# 4_Interface2.net
KiCad netlist of a schematic drawn in Altium Designer
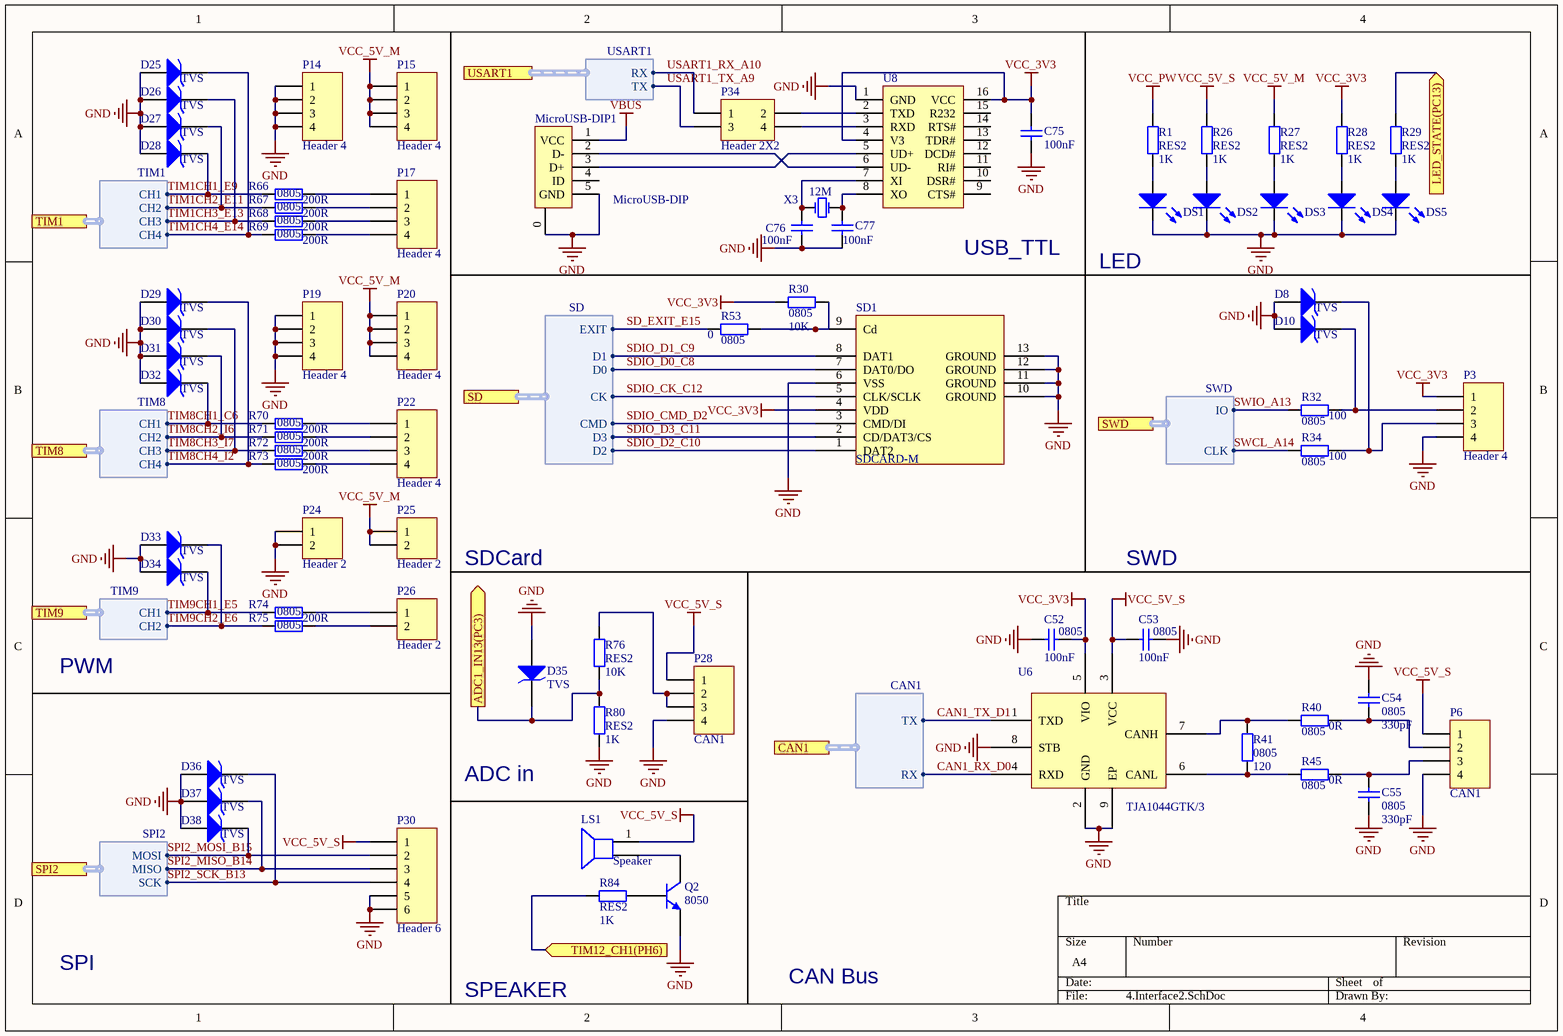
[diagram p0: 4.Interface2.SchDoc]

(export (version "E")
  (design (tool "Eeschema 10.0.6"))
  (components
    (comp (ref "C52")
      (value "0805")
      (footprint "C 0805_M")
      (fields (field (name "ALTIUM_VALUE") "100nF"))
      (libsource (lib "QT") (part "CAP"))
    )
    (comp (ref "C53")
      (value "0805")
      (footprint "C 0805_M")
      (fields (field (name "ALTIUM_VALUE") "100nF"))
      (libsource (lib "QT") (part "CAP"))
    )
    (comp (ref "C54")
      (value "0805")
      (footprint "C 0805_M")
      (fields (field (name "ALTIUM_VALUE") "330pF"))
      (libsource (lib "QT") (part "CAP"))
    )
    (comp (ref "C55")
      (value "0805")
      (footprint "C 0805_M")
      (fields (field (name "ALTIUM_VALUE") "330pF"))
      (libsource (lib "QT") (part "CAP"))
    )
    (comp (ref "C75")
      (value "100nF")
      (footprint "C 0805_L")
      (fields (field (name "Comment") "CAP"))
      (libsource (lib "QT") (part "CAP"))
    )
    (comp (ref "C76")
      (value "100nF")
      (footprint "C 0805_L")
      (fields (field (name "Comment") "CAP"))
      (libsource (lib "QT") (part "CAP"))
    )
    (comp (ref "C77")
      (value "100nF")
      (footprint "C 0805_L")
      (fields (field (name "Comment") "CAP"))
      (libsource (lib "QT") (part "CAP"))
    )
    (comp (ref "D8")
      (value "TVS")
      (footprint "SOD-523")
      (description "High Conductance Fast Diode")
      (fields (field (name "PUBLISHER") "Altium Limited"))
      (libsource (lib "QT") (part "D"))
    )
    (comp (ref "D10")
      (value "TVS")
      (footprint "SOD-523")
      (description "High Conductance Fast Diode")
      (fields (field (name "PUBLISHER") "Altium Limited"))
      (libsource (lib "QT") (part "D"))
    )
    (comp (ref "D25")
      (value "TVS")
      (footprint "SOD-523")
      (description "High Conductance Fast Diode")
      (fields (field (name "PUBLISHER") "Altium Limited"))
      (libsource (lib "QT") (part "D"))
    )
    (comp (ref "D26")
      (value "TVS")
      (footprint "SOD-523")
      (description "High Conductance Fast Diode")
      (fields (field (name "PUBLISHER") "Altium Limited"))
      (libsource (lib "QT") (part "D"))
    )
    (comp (ref "D27")
      (value "TVS")
      (footprint "SOD-523")
      (description "High Conductance Fast Diode")
      (fields (field (name "PUBLISHER") "Altium Limited"))
      (libsource (lib "QT") (part "D"))
    )
    (comp (ref "D28")
      (value "TVS")
      (footprint "SOD-523")
      (description "High Conductance Fast Diode")
      (fields (field (name "PUBLISHER") "Altium Limited"))
      (libsource (lib "QT") (part "D"))
    )
    (comp (ref "D29")
      (value "TVS")
      (footprint "SOD-523")
      (description "High Conductance Fast Diode")
      (fields (field (name "PUBLISHER") "Altium Limited"))
      (libsource (lib "QT") (part "D"))
    )
    (comp (ref "D30")
      (value "TVS")
      (footprint "SOD-523")
      (description "High Conductance Fast Diode")
      (fields (field (name "PUBLISHER") "Altium Limited"))
      (libsource (lib "QT") (part "D"))
    )
    (comp (ref "D31")
      (value "TVS")
      (footprint "SOD-523")
      (description "High Conductance Fast Diode")
      (fields (field (name "PUBLISHER") "Altium Limited"))
      (libsource (lib "QT") (part "D"))
    )
    (comp (ref "D32")
      (value "TVS")
      (footprint "SOD-523")
      (description "High Conductance Fast Diode")
      (fields (field (name "PUBLISHER") "Altium Limited"))
      (libsource (lib "QT") (part "D"))
    )
    (comp (ref "D33")
      (value "TVS")
      (footprint "SOD-523")
      (description "High Conductance Fast Diode")
      (fields (field (name "PUBLISHER") "Altium Limited"))
      (libsource (lib "QT") (part "D"))
    )
    (comp (ref "D34")
      (value "TVS")
      (footprint "SOD-523")
      (description "High Conductance Fast Diode")
      (fields (field (name "PUBLISHER") "Altium Limited"))
      (libsource (lib "QT") (part "D"))
    )
    (comp (ref "D35")
      (value "TVS")
      (footprint "SOD-523")
      (description "High Conductance Fast Diode")
      (fields (field (name "PUBLISHER") "Altium Limited"))
      (libsource (lib "QT") (part "D"))
    )
    (comp (ref "D36")
      (value "TVS")
      (footprint "SOD-523")
      (description "High Conductance Fast Diode")
      (fields (field (name "PUBLISHER") "Altium Limited"))
      (libsource (lib "QT") (part "D"))
    )
    (comp (ref "D37")
      (value "TVS")
      (footprint "SOD-523")
      (description "High Conductance Fast Diode")
      (fields (field (name "PUBLISHER") "Altium Limited"))
      (libsource (lib "QT") (part "D"))
    )
    (comp (ref "D38")
      (value "TVS")
      (footprint "SOD-523")
      (description "High Conductance Fast Diode")
      (fields (field (name "PUBLISHER") "Altium Limited"))
      (libsource (lib "QT") (part "D"))
    )
    (comp (ref "DS1") (value "LED") (footprint "LED 0805B") (libsource (lib "QT") (part "LED")))
    (comp (ref "DS2") (value "LED") (footprint "LED 0805B") (libsource (lib "QT") (part "LED")))
    (comp (ref "DS3") (value "LED") (footprint "LED 0805B") (libsource (lib "QT") (part "LED")))
    (comp (ref "DS4") (value "LED") (footprint "LED 0805B") (libsource (lib "QT") (part "LED")))
    (comp (ref "DS5") (value "LED") (footprint "LED 0805B") (libsource (lib "QT") (part "LED")))
    (comp (ref "LS1")
      (value "Speaker")
      (footprint "BEEP 5x9x5.5")
      (description "Loudspeaker")
      (fields (field (name "PUBLISHER") "Altium Limited"))
      (libsource (lib "QT") (part "Speaker"))
    )
    (comp (ref "MicroUSB-DIP1")
      (value "MicroUSB-DIP")
      (footprint "MICRO_USB_DIP")
      (libsource (lib "PineapplePi-F1") (part "MicroUSB-DIP"))
    )
    (comp (ref "P3")
      (value "Header 4")
      (footprint "KF2EDGK-2.54-WI-4P")
      (description "Header, 4-Pin")
      (fields (field (name "PUBLISHER") "Altium Limited"))
      (libsource (lib "QT") (part "Header 4"))
    )
    (comp (ref "P6")
      (value "CAN1")
      (footprint "KF2EDGK-2.54-WI-4P")
      (description "Header, 4-Pin")
      (fields (field (name "PUBLISHER") "Altium Limited"))
      (libsource (lib "QT") (part "Header 4"))
    )
    (comp (ref "P14")
      (value "Header 4")
      (footprint "HDR2.54-LI-4P")
      (description "Header, 4-Pin")
      (fields (field (name "PUBLISHER") "Altium Limited"))
      (libsource (lib "QT") (part "Header 4"))
    )
    (comp (ref "P15")
      (value "Header 4")
      (footprint "HDR2.54-LI-4P")
      (description "Header, 4-Pin")
      (fields (field (name "PUBLISHER") "Altium Limited"))
      (libsource (lib "QT") (part "Header 4"))
    )
    (comp (ref "P17")
      (value "Header 4")
      (footprint "HDR2.54-LI-4P")
      (description "Header, 4-Pin")
      (fields (field (name "PUBLISHER") "Altium Limited"))
      (libsource (lib "QT") (part "Header 4"))
    )
    (comp (ref "P19")
      (value "Header 4")
      (footprint "HDR2.54-LI-4P")
      (description "Header, 4-Pin")
      (fields (field (name "PUBLISHER") "Altium Limited"))
      (libsource (lib "QT") (part "Header 4"))
    )
    (comp (ref "P20")
      (value "Header 4")
      (footprint "HDR2.54-LI-4P")
      (description "Header, 4-Pin")
      (fields (field (name "PUBLISHER") "Altium Limited"))
      (libsource (lib "QT") (part "Header 4"))
    )
    (comp (ref "P22")
      (value "Header 4")
      (footprint "HDR2.54-LI-4P")
      (description "Header, 4-Pin")
      (fields (field (name "PUBLISHER") "Altium Limited"))
      (libsource (lib "QT") (part "Header 4"))
    )
    (comp (ref "P24")
      (value "Header 2")
      (footprint "HDR2.54-LI-2P")
      (description "Header, 2-Pin")
      (fields (field (name "PUBLISHER") "Altium Limited"))
      (libsource (lib "QT") (part "Header 2"))
    )
    (comp (ref "P25")
      (value "Header 2")
      (footprint "HDR2.54-LI-2P")
      (description "Header, 2-Pin")
      (fields (field (name "PUBLISHER") "Altium Limited"))
      (libsource (lib "QT") (part "Header 2"))
    )
    (comp (ref "P26")
      (value "Header 2")
      (footprint "HDR2.54-LI-2P")
      (description "Header, 2-Pin")
      (fields (field (name "PUBLISHER") "Altium Limited"))
      (libsource (lib "QT") (part "Header 2"))
    )
    (comp (ref "P28")
      (value "CAN1")
      (footprint "KF2EDGK-2.54-WI-4P")
      (description "Header, 4-Pin")
      (fields (field (name "PUBLISHER") "Altium Limited"))
      (libsource (lib "QT") (part "Header 4"))
    )
    (comp (ref "P30")
      (value "Header 6")
      (footprint "KF2EDGK-2.54-WI-6P")
      (description "Header, 6-Pin")
      (fields (field (name "PUBLISHER") "Altium Limited"))
      (libsource (lib "Miscellaneous Connectors") (part "Header 6"))
    )
    (comp (ref "P34")
      (value "Header 2X2")
      (footprint "HDR2.54-LI-2x2P")
      (description "Header, 2-Pin, Dual row")
      (fields (field (name "PUBLISHER") "Altium Limited"))
      (libsource (lib "QT") (part "Header 2X2"))
    )
    (comp (ref "Q2")
      (value "8050")
      (footprint "SOT23-3L")
      (description "NPN Bipolar Transistor")
      (fields (field (name "PUBLISHER") "Altium Limited"))
      (libsource (lib "QT") (part "NPN  SOT"))
    )
    (comp (ref "R1")
      (value "RES2")
      (footprint "R 0805_L")
      (description "Resistor")
      (fields (field (name "ALTIUM_VALUE") "1K") (field (name "PUBLISHER") "Altium Limited"))
      (libsource (lib "") (part "RES2_1"))
    )
    (comp (ref "R26")
      (value "RES2")
      (footprint "R 0805_L")
      (description "Resistor")
      (fields (field (name "ALTIUM_VALUE") "1K") (field (name "PUBLISHER") "Altium Limited"))
      (libsource (lib "") (part "RES2_1"))
    )
    (comp (ref "R27")
      (value "RES2")
      (footprint "R 0805_L")
      (description "Resistor")
      (fields (field (name "ALTIUM_VALUE") "1K") (field (name "PUBLISHER") "Altium Limited"))
      (libsource (lib "") (part "RES2_1"))
    )
    (comp (ref "R28")
      (value "RES2")
      (footprint "R 0805_L")
      (description "Resistor")
      (fields (field (name "ALTIUM_VALUE") "1K") (field (name "PUBLISHER") "Altium Limited"))
      (libsource (lib "") (part "RES2_1"))
    )
    (comp (ref "R29")
      (value "RES2")
      (footprint "R 0805_L")
      (description "Resistor")
      (fields (field (name "ALTIUM_VALUE") "1K") (field (name "PUBLISHER") "Altium Limited"))
      (libsource (lib "") (part "RES2_1"))
    )
    (comp (ref "R30")
      (value "0805")
      (footprint "R 0805_L")
      (description "Resistor")
      (fields (field (name "ALTIUM_VALUE") "10K") (field (name "PUBLISHER") "Altium Limited"))
      (libsource (lib "QT") (part "RES2"))
    )
    (comp (ref "R32")
      (value "0805")
      (footprint "R 0805_L")
      (description "Resistor")
      (fields (field (name "ALTIUM_VALUE") "100") (field (name "PUBLISHER") "Altium Limited"))
      (libsource (lib "") (part "RES2_2"))
    )
    (comp (ref "R34")
      (value "0805")
      (footprint "R 0805_L")
      (description "Resistor")
      (fields (field (name "ALTIUM_VALUE") "100") (field (name "PUBLISHER") "Altium Limited"))
      (libsource (lib "") (part "RES2_2"))
    )
    (comp (ref "R40")
      (value "0805")
      (footprint "R 0805_L")
      (description "Resistor")
      (fields (field (name "ALTIUM_VALUE") "0R") (field (name "PUBLISHER") "Altium Limited"))
      (libsource (lib "QT") (part "RES2"))
    )
    (comp (ref "R41")
      (value "0805")
      (footprint "R 0805_L")
      (description "Resistor")
      (fields (field (name "ALTIUM_VALUE") "120") (field (name "PUBLISHER") "Altium Limited"))
      (libsource (lib "") (part "RES2_1"))
    )
    (comp (ref "R45")
      (value "0805")
      (footprint "R 0805_L")
      (description "Resistor")
      (fields (field (name "ALTIUM_VALUE") "0R") (field (name "PUBLISHER") "Altium Limited"))
      (libsource (lib "QT") (part "RES2"))
    )
    (comp (ref "R53")
      (value "0805")
      (footprint "R 0805_L")
      (description "Resistor")
      (fields (field (name "ALTIUM_VALUE") "0") (field (name "PUBLISHER") "Altium Limited"))
      (libsource (lib "") (part "RES2_2"))
    )
    (comp (ref "R66")
      (value "0805")
      (footprint "R 0805_L")
      (description "Resistor")
      (fields (field (name "ALTIUM_VALUE") "200R") (field (name "PUBLISHER") "Altium Limited"))
      (libsource (lib "") (part "RES2_2"))
    )
    (comp (ref "R67")
      (value "0805")
      (footprint "R 0805_L")
      (description "Resistor")
      (fields (field (name "ALTIUM_VALUE") "200R") (field (name "PUBLISHER") "Altium Limited"))
      (libsource (lib "") (part "RES2_2"))
    )
    (comp (ref "R68")
      (value "0805")
      (footprint "R 0805_L")
      (description "Resistor")
      (fields (field (name "ALTIUM_VALUE") "200R") (field (name "PUBLISHER") "Altium Limited"))
      (libsource (lib "") (part "RES2_2"))
    )
    (comp (ref "R69")
      (value "0805")
      (footprint "R 0805_L")
      (description "Resistor")
      (fields (field (name "ALTIUM_VALUE") "200R") (field (name "PUBLISHER") "Altium Limited"))
      (libsource (lib "") (part "RES2_2"))
    )
    (comp (ref "R70")
      (value "0805")
      (footprint "R 0805_L")
      (description "Resistor")
      (fields (field (name "ALTIUM_VALUE") "200R") (field (name "PUBLISHER") "Altium Limited"))
      (libsource (lib "") (part "RES2_2"))
    )
    (comp (ref "R71")
      (value "0805")
      (footprint "R 0805_L")
      (description "Resistor")
      (fields (field (name "ALTIUM_VALUE") "200R") (field (name "PUBLISHER") "Altium Limited"))
      (libsource (lib "") (part "RES2_2"))
    )
    (comp (ref "R72")
      (value "0805")
      (footprint "R 0805_L")
      (description "Resistor")
      (fields (field (name "ALTIUM_VALUE") "200R") (field (name "PUBLISHER") "Altium Limited"))
      (libsource (lib "") (part "RES2_2"))
    )
    (comp (ref "R73")
      (value "0805")
      (footprint "R 0805_L")
      (description "Resistor")
      (fields (field (name "ALTIUM_VALUE") "200R") (field (name "PUBLISHER") "Altium Limited"))
      (libsource (lib "") (part "RES2_2"))
    )
    (comp (ref "R74")
      (value "0805")
      (footprint "R 0805_L")
      (description "Resistor")
      (fields (field (name "ALTIUM_VALUE") "200R") (field (name "PUBLISHER") "Altium Limited"))
      (libsource (lib "") (part "RES2_2"))
    )
    (comp (ref "R75")
      (value "0805")
      (footprint "R 0805_L")
      (description "Resistor")
      (fields (field (name "PUBLISHER") "Altium Limited"))
      (libsource (lib "") (part "RES2_2"))
    )
    (comp (ref "R76")
      (value "RES2")
      (footprint "R 0805_L")
      (description "Resistor")
      (fields (field (name "ALTIUM_VALUE") "10K") (field (name "PUBLISHER") "Altium Limited"))
      (libsource (lib "") (part "RES2_1"))
    )
    (comp (ref "R80")
      (value "RES2")
      (footprint "R 0805_L")
      (description "Resistor")
      (fields (field (name "ALTIUM_VALUE") "1K") (field (name "PUBLISHER") "Altium Limited"))
      (libsource (lib "") (part "RES2_1"))
    )
    (comp (ref "R84")
      (value "RES2")
      (footprint "R 0805_L")
      (description "Resistor")
      (fields (field (name "ALTIUM_VALUE") "1K") (field (name "PUBLISHER") "Altium Limited"))
      (libsource (lib "QT") (part "RES2"))
    )
    (comp (ref "SD1")
      (value "SDCARD-M")
      (footprint "SDCARD-M")
      (description "TF卡槽")
      (libsource (lib "Fszhang") (part "SDCARD-M"))
    )
    (comp (ref "U6")
      (value "TJA1044GTK/3")
      (footprint "HVSON8")
      (libsource (lib "常用元件库") (part "TJA1044GTK/3"))
    )
    (comp (ref "U8") (value "CH340G") (footprint "SOP16_M") (libsource (lib "史福祥库") (part "CH340G")))
    (comp (ref "X3") (value "12M") (footprint "OSC HC-49S") (libsource (lib "QT") (part "YX")))
  )
  (nets
    (net (code "9") (name "/ADC1_IN13(PC3)") (class "Default")
      (node (ref "D35") (pin "2") (pinfunction "K_2") (pintype "passive"))
      (node (ref "R76") (pin "1") (pinfunction "1_1") (pintype "passive"))
      (node (ref "R80") (pin "2") (pinfunction "2_2") (pintype "passive"))
    )
    (net (code "10") (name "/CAN1_RX_D0") (class "Default")
      (node (ref "U6") (pin "4") (pinfunction "RXD_4") (pintype "passive"))
    )
    (net (code "11") (name "/CAN1_TX_D1") (class "Default")
      (node (ref "U6") (pin "1") (pinfunction "TXD_1") (pintype "passive"))
    )
    (net (code "12") (name "/LED_STATE(PC13)") (class "Default")
      (node (ref "R29") (pin "2") (pinfunction "2_2") (pintype "passive"))
    )
    (net (code "13") (name "/SDIO_CK_C12") (class "Default")
      (node (ref "SD1") (pin "5") (pinfunction "CLK/SCLK_5") (pintype "passive"))
    )
    (net (code "14") (name "/SDIO_CMD_D2") (class "Default")
      (node (ref "SD1") (pin "3") (pinfunction "CMD/DI_3") (pintype "passive"))
    )
    (net (code "15") (name "/SDIO_D0_C8") (class "Default")
      (node (ref "SD1") (pin "7") (pinfunction "DAT0/DO_7") (pintype "passive"))
    )
    (net (code "16") (name "/SDIO_D1_C9") (class "Default")
      (node (ref "SD1") (pin "8") (pinfunction "DAT1_8") (pintype "passive"))
    )
    (net (code "17") (name "/SDIO_D2_C10") (class "Default")
      (node (ref "SD1") (pin "1") (pinfunction "DAT2_1") (pintype "passive"))
    )
    (net (code "18") (name "/SDIO_D3_C11") (class "Default")
      (node (ref "SD1") (pin "2") (pinfunction "CD/DAT3/CS_2") (pintype "passive"))
    )
    (net (code "19") (name "/SD_EXIT_E15") (class "Default")
      (node (ref "R53") (pin "1") (pinfunction "1_1") (pintype "passive"))
    )
    (net (code "20") (name "/SPI2_MISO_B14") (class "Default")
      (node (ref "D37") (pin "2") (pinfunction "K_2") (pintype "passive"))
      (node (ref "P30") (pin "3") (pinfunction "3_3") (pintype "passive"))
    )
    (net (code "21") (name "/SPI2_MOSI_B15") (class "Default")
      (node (ref "D38") (pin "2") (pinfunction "K_2") (pintype "passive"))
      (node (ref "P30") (pin "2") (pinfunction "2_2") (pintype "passive"))
    )
    (net (code "22") (name "/SPI2_SCK_B13") (class "Default")
      (node (ref "D36") (pin "2") (pinfunction "K_2") (pintype "passive"))
      (node (ref "P30") (pin "4") (pinfunction "4_4") (pintype "passive"))
    )
    (net (code "23") (name "/SWCL_A14") (class "Default")
      (node (ref "R34") (pin "1") (pinfunction "1_1") (pintype "passive"))
    )
    (net (code "24") (name "/SWIO_A13") (class "Default")
      (node (ref "R32") (pin "1") (pinfunction "1_1") (pintype "passive"))
    )
    (net (code "25") (name "/TIM1CH1_E9") (class "Default")
      (node (ref "D28") (pin "2") (pinfunction "K_2") (pintype "passive"))
      (node (ref "R66") (pin "1") (pinfunction "1_1") (pintype "passive"))
    )
    (net (code "26") (name "/TIM1CH2_E11") (class "Default")
      (node (ref "D27") (pin "2") (pinfunction "K_2") (pintype "passive"))
      (node (ref "R67") (pin "1") (pinfunction "1_1") (pintype "passive"))
    )
    (net (code "27") (name "/TIM1CH3_E13") (class "Default")
      (node (ref "D26") (pin "2") (pinfunction "K_2") (pintype "passive"))
      (node (ref "R68") (pin "1") (pinfunction "1_1") (pintype "passive"))
    )
    (net (code "28") (name "/TIM1CH4_E14") (class "Default")
      (node (ref "D25") (pin "2") (pinfunction "K_2") (pintype "passive"))
      (node (ref "R69") (pin "1") (pinfunction "1_1") (pintype "passive"))
    )
    (net (code "29") (name "/TIM8CH1_C6") (class "Default")
      (node (ref "D32") (pin "2") (pinfunction "K_2") (pintype "passive"))
      (node (ref "R70") (pin "1") (pinfunction "1_1") (pintype "passive"))
    )
    (net (code "30") (name "/TIM8CH2_I6") (class "Default")
      (node (ref "D31") (pin "2") (pinfunction "K_2") (pintype "passive"))
      (node (ref "R71") (pin "1") (pinfunction "1_1") (pintype "passive"))
    )
    (net (code "31") (name "/TIM8CH3_I7") (class "Default")
      (node (ref "D30") (pin "2") (pinfunction "K_2") (pintype "passive"))
      (node (ref "R72") (pin "1") (pinfunction "1_1") (pintype "passive"))
    )
    (net (code "32") (name "/TIM8CH4_I2") (class "Default")
      (node (ref "D29") (pin "2") (pinfunction "K_2") (pintype "passive"))
      (node (ref "R73") (pin "1") (pinfunction "1_1") (pintype "passive"))
    )
    (net (code "33") (name "/TIM9CH1_E5") (class "Default")
      (node (ref "D34") (pin "2") (pinfunction "K_2") (pintype "passive"))
      (node (ref "R74") (pin "1") (pinfunction "1_1") (pintype "passive"))
    )
    (net (code "34") (name "/TIM9CH2_E6") (class "Default")
      (node (ref "D33") (pin "2") (pinfunction "K_2") (pintype "passive"))
      (node (ref "R75") (pin "1") (pinfunction "1_1") (pintype "passive"))
    )
    (net (code "35") (name "/TIM12_CH1(PH6)") (class "Default")
      (node (ref "R84") (pin "2") (pinfunction "2_2") (pintype "passive"))
    )
    (net (code "36") (name "/USART1_RX_A10") (class "Default")
      (node (ref "P34") (pin "1") (pinfunction "1_1") (pintype "passive"))
    )
    (net (code "37") (name "/USART1_TX_A9") (class "Default")
      (node (ref "P34") (pin "3") (pinfunction "3_3") (pintype "passive"))
    )
    (net (code "46") (name "GND") (class "Default")
      (node (ref "C52") (pin "1") (pinfunction "1_1") (pintype "passive"))
      (node (ref "C53") (pin "2") (pinfunction "2_2") (pintype "passive"))
      (node (ref "C54") (pin "2") (pinfunction "2_2") (pintype "passive"))
      (node (ref "C55") (pin "1") (pinfunction "1_1") (pintype "passive"))
      (node (ref "C75") (pin "1") (pinfunction "1_1") (pintype "passive"))
      (node (ref "C76") (pin "1") (pinfunction "1_1") (pintype "passive"))
      (node (ref "C77") (pin "1") (pinfunction "1_1") (pintype "passive"))
      (node (ref "D10") (pin "1") (pinfunction "A_1") (pintype "passive"))
      (node (ref "D25") (pin "1") (pinfunction "A_1") (pintype "passive"))
      (node (ref "D26") (pin "1") (pinfunction "A_1") (pintype "passive"))
      (node (ref "D27") (pin "1") (pinfunction "A_1") (pintype "passive"))
      (node (ref "D28") (pin "1") (pinfunction "A_1") (pintype "passive"))
      (node (ref "D29") (pin "1") (pinfunction "A_1") (pintype "passive"))
      (node (ref "D30") (pin "1") (pinfunction "A_1") (pintype "passive"))
      (node (ref "D31") (pin "1") (pinfunction "A_1") (pintype "passive"))
      (node (ref "D32") (pin "1") (pinfunction "A_1") (pintype "passive"))
      (node (ref "D33") (pin "1") (pinfunction "A_1") (pintype "passive"))
      (node (ref "D34") (pin "1") (pinfunction "A_1") (pintype "passive"))
      (node (ref "D35") (pin "1") (pinfunction "A_1") (pintype "passive"))
      (node (ref "D36") (pin "1") (pinfunction "A_1") (pintype "passive"))
      (node (ref "D37") (pin "1") (pinfunction "A_1") (pintype "passive"))
      (node (ref "D38") (pin "1") (pinfunction "A_1") (pintype "passive"))
      (node (ref "D8") (pin "1") (pinfunction "A_1") (pintype "passive"))
      (node (ref "DS1") (pin "2") (pinfunction "K_2") (pintype "passive"))
      (node (ref "DS2") (pin "2") (pinfunction "K_2") (pintype "passive"))
      (node (ref "DS3") (pin "2") (pinfunction "K_2") (pintype "passive"))
      (node (ref "DS4") (pin "2") (pinfunction "K_2") (pintype "passive"))
      (node (ref "DS5") (pin "2") (pinfunction "K_2") (pintype "passive"))
      (node (ref "MicroUSB-DIP1") (pin "0") (pintype "passive"))
      (node (ref "MicroUSB-DIP1") (pin "5") (pinfunction "GND_5") (pintype "power_in"))
      (node (ref "P14") (pin "1") (pinfunction "1_1") (pintype "passive"))
      (node (ref "P14") (pin "2") (pinfunction "2_2") (pintype "passive"))
      (node (ref "P14") (pin "3") (pinfunction "3_3") (pintype "passive"))
      (node (ref "P14") (pin "4") (pinfunction "4_4") (pintype "passive"))
      (node (ref "P19") (pin "1") (pinfunction "1_1") (pintype "passive"))
      (node (ref "P19") (pin "2") (pinfunction "2_2") (pintype "passive"))
      (node (ref "P19") (pin "3") (pinfunction "3_3") (pintype "passive"))
      (node (ref "P19") (pin "4") (pinfunction "4_4") (pintype "passive"))
      (node (ref "P24") (pin "1") (pinfunction "1_1") (pintype "passive"))
      (node (ref "P24") (pin "2") (pinfunction "2_2") (pintype "passive"))
      (node (ref "P28") (pin "4") (pinfunction "4_4") (pintype "passive"))
      (node (ref "P3") (pin "4") (pinfunction "4_4") (pintype "passive"))
      (node (ref "P30") (pin "5") (pinfunction "5_5") (pintype "passive"))
      (node (ref "P30") (pin "6") (pinfunction "6_6") (pintype "passive"))
      (node (ref "P6") (pin "4") (pinfunction "4_4") (pintype "passive"))
      (node (ref "Q2") (pin "2") (pinfunction "E_2") (pintype "passive"))
      (node (ref "R80") (pin "1") (pinfunction "1_1") (pintype "passive"))
      (node (ref "SD1") (pin "10") (pinfunction "GROUND_10") (pintype "passive"))
      (node (ref "SD1") (pin "11") (pinfunction "GROUND_11") (pintype "passive"))
      (node (ref "SD1") (pin "12") (pinfunction "GROUND_12") (pintype "passive"))
      (node (ref "SD1") (pin "13") (pinfunction "GROUND_13") (pintype "passive"))
      (node (ref "SD1") (pin "6") (pinfunction "VSS_6") (pintype "passive"))
      (node (ref "U6") (pin "2") (pinfunction "GND_2") (pintype "passive"))
      (node (ref "U6") (pin "8") (pinfunction "STB_8") (pintype "passive"))
      (node (ref "U6") (pin "9") (pinfunction "EP_9") (pintype "passive"))
      (node (ref "U8") (pin "1") (pinfunction "GND_1") (pintype "passive"))
    )
    (net (code "47") (name "Net-(C54-Pad1)") (class "Default")
      (node (ref "C54") (pin "1") (pinfunction "1_1") (pintype "passive"))
      (node (ref "P6") (pin "2") (pinfunction "2_2") (pintype "passive"))
      (node (ref "R40") (pin "1") (pinfunction "1_1") (pintype "passive"))
    )
    (net (code "48") (name "Net-(C55-Pad2)") (class "Default")
      (node (ref "C55") (pin "2") (pinfunction "2_2") (pintype "passive"))
      (node (ref "P6") (pin "3") (pinfunction "3_3") (pintype "passive"))
      (node (ref "R45") (pin "1") (pinfunction "1_1") (pintype "passive"))
    )
    (net (code "49") (name "Net-(D8-K)") (class "Default")
      (node (ref "D8") (pin "2") (pinfunction "K_2") (pintype "passive"))
      (node (ref "P3") (pin "3") (pinfunction "3_3") (pintype "passive"))
      (node (ref "R34") (pin "2") (pinfunction "2_2") (pintype "passive"))
    )
    (net (code "50") (name "Net-(D10-K)") (class "Default")
      (node (ref "D10") (pin "2") (pinfunction "K_2") (pintype "passive"))
      (node (ref "P3") (pin "2") (pinfunction "2_2") (pintype "passive"))
      (node (ref "R32") (pin "2") (pinfunction "2_2") (pintype "passive"))
    )
    (net (code "51") (name "Net-(DS1-A)") (class "Default")
      (node (ref "DS1") (pin "1") (pinfunction "A_1") (pintype "passive"))
      (node (ref "R1") (pin "1") (pinfunction "1_1") (pintype "passive"))
    )
    (net (code "52") (name "Net-(DS2-A)") (class "Default")
      (node (ref "DS2") (pin "1") (pinfunction "A_1") (pintype "passive"))
      (node (ref "R26") (pin "1") (pinfunction "1_1") (pintype "passive"))
    )
    (net (code "53") (name "Net-(DS3-A)") (class "Default")
      (node (ref "DS3") (pin "1") (pinfunction "A_1") (pintype "passive"))
      (node (ref "R27") (pin "1") (pinfunction "1_1") (pintype "passive"))
    )
    (net (code "54") (name "Net-(DS4-A)") (class "Default")
      (node (ref "DS4") (pin "1") (pinfunction "A_1") (pintype "passive"))
      (node (ref "R28") (pin "1") (pinfunction "1_1") (pintype "passive"))
    )
    (net (code "55") (name "Net-(DS5-A)") (class "Default")
      (node (ref "DS5") (pin "1") (pinfunction "A_1") (pintype "passive"))
      (node (ref "R29") (pin "1") (pinfunction "1_1") (pintype "passive"))
    )
    (net (code "56") (name "Net-(MicroUSB-DIP1-D+)") (class "Default")
      (node (ref "MicroUSB-DIP1") (pin "3") (pinfunction "D+_3") (pintype "power_in"))
      (node (ref "U8") (pin "5") (pinfunction "UD+_5") (pintype "passive"))
    )
    (net (code "57") (name "Net-(MicroUSB-DIP1-D-)") (class "Default")
      (node (ref "MicroUSB-DIP1") (pin "2") (pinfunction "D-_2") (pintype "power_in"))
      (node (ref "U8") (pin "6") (pinfunction "UD-_6") (pintype "passive"))
    )
    (net (code "58") (name "Net-(P17-Pad1)") (class "Default")
      (node (ref "P17") (pin "1") (pinfunction "1_1") (pintype "passive"))
      (node (ref "R66") (pin "2") (pinfunction "2_2") (pintype "passive"))
    )
    (net (code "59") (name "Net-(P17-Pad2)") (class "Default")
      (node (ref "P17") (pin "2") (pinfunction "2_2") (pintype "passive"))
      (node (ref "R67") (pin "2") (pinfunction "2_2") (pintype "passive"))
    )
    (net (code "60") (name "Net-(P17-Pad3)") (class "Default")
      (node (ref "P17") (pin "3") (pinfunction "3_3") (pintype "passive"))
      (node (ref "R68") (pin "2") (pinfunction "2_2") (pintype "passive"))
    )
    (net (code "61") (name "Net-(P17-Pad4)") (class "Default")
      (node (ref "P17") (pin "4") (pinfunction "4_4") (pintype "passive"))
      (node (ref "R69") (pin "2") (pinfunction "2_2") (pintype "passive"))
    )
    (net (code "62") (name "Net-(P22-Pad1)") (class "Default")
      (node (ref "P22") (pin "1") (pinfunction "1_1") (pintype "passive"))
      (node (ref "R70") (pin "2") (pinfunction "2_2") (pintype "passive"))
    )
    (net (code "63") (name "Net-(P22-Pad2)") (class "Default")
      (node (ref "P22") (pin "2") (pinfunction "2_2") (pintype "passive"))
      (node (ref "R71") (pin "2") (pinfunction "2_2") (pintype "passive"))
    )
    (net (code "64") (name "Net-(P22-Pad3)") (class "Default")
      (node (ref "P22") (pin "3") (pinfunction "3_3") (pintype "passive"))
      (node (ref "R72") (pin "2") (pinfunction "2_2") (pintype "passive"))
    )
    (net (code "65") (name "Net-(P22-Pad4)") (class "Default")
      (node (ref "P22") (pin "4") (pinfunction "4_4") (pintype "passive"))
      (node (ref "R73") (pin "2") (pinfunction "2_2") (pintype "passive"))
    )
    (net (code "66") (name "Net-(P26-Pad1)") (class "Default")
      (node (ref "P26") (pin "1") (pinfunction "1_1") (pintype "passive"))
      (node (ref "R74") (pin "2") (pinfunction "2_2") (pintype "passive"))
    )
    (net (code "67") (name "Net-(P26-Pad2)") (class "Default")
      (node (ref "P26") (pin "2") (pinfunction "2_2") (pintype "passive"))
      (node (ref "R75") (pin "2") (pinfunction "2_2") (pintype "passive"))
    )
    (net (code "68") (name "Net-(P28-Pad2)") (class "Default")
      (node (ref "P28") (pin "2") (pinfunction "2_2") (pintype "passive"))
      (node (ref "P28") (pin "3") (pinfunction "3_3") (pintype "passive"))
      (node (ref "R76") (pin "2") (pinfunction "2_2") (pintype "passive"))
    )
    (net (code "69") (name "Net-(Q2-B)") (class "Default")
      (node (ref "Q2") (pin "1") (pinfunction "B_1") (pintype "passive"))
      (node (ref "R84") (pin "1") (pinfunction "1_1") (pintype "passive"))
    )
    (net (code "70") (name "Net-(Q2-C)") (class "Default")
      (node (ref "LS1") (pin "2") (pinfunction "2_2") (pintype "passive"))
      (node (ref "Q2") (pin "3") (pinfunction "C_3") (pintype "passive"))
    )
    (net (code "71") (name "Net-(SD1-Cd)") (class "Default")
      (node (ref "R30") (pin "1") (pinfunction "1_1") (pintype "passive"))
      (node (ref "R53") (pin "2") (pinfunction "2_2") (pintype "passive"))
      (node (ref "SD1") (pin "9") (pinfunction "Cd_9") (pintype "passive"))
    )
    (net (code "72") (name "Net-(U6-CANH)") (class "Default")
      (node (ref "R40") (pin "2") (pinfunction "2_2") (pintype "passive"))
      (node (ref "R41") (pin "2") (pinfunction "2_2") (pintype "passive"))
      (node (ref "U6") (pin "7") (pinfunction "CANH_7") (pintype "passive"))
    )
    (net (code "73") (name "Net-(U6-CANL)") (class "Default")
      (node (ref "R41") (pin "1") (pinfunction "1_1") (pintype "passive"))
      (node (ref "R45") (pin "2") (pinfunction "2_2") (pintype "passive"))
      (node (ref "U6") (pin "6") (pinfunction "CANL_6") (pintype "passive"))
    )
    (net (code "74") (name "Net-(U8-RXD)") (class "Default")
      (node (ref "P34") (pin "4") (pinfunction "4_4") (pintype "passive"))
      (node (ref "U8") (pin "3") (pinfunction "RXD_3") (pintype "passive"))
    )
    (net (code "75") (name "Net-(U8-TXD)") (class "Default")
      (node (ref "P34") (pin "2") (pinfunction "2_2") (pintype "passive"))
      (node (ref "U8") (pin "2") (pinfunction "TXD_2") (pintype "passive"))
    )
    (net (code "76") (name "Net-(U8-XI)") (class "Default")
      (node (ref "C76") (pin "2") (pinfunction "2_2") (pintype "passive"))
      (node (ref "U8") (pin "7") (pinfunction "XI_7") (pintype "passive"))
      (node (ref "X3") (pin "1") (pinfunction "OSC1_1") (pintype "passive"))
    )
    (net (code "77") (name "Net-(U8-XO)") (class "Default")
      (node (ref "C77") (pin "2") (pinfunction "2_2") (pintype "passive"))
      (node (ref "U8") (pin "8") (pinfunction "XO_8") (pintype "passive"))
      (node (ref "X3") (pin "2") (pinfunction "OSC2_2") (pintype "passive"))
    )
    (net (code "78") (name "VBUS") (class "Default")
      (node (ref "MicroUSB-DIP1") (pin "1") (pinfunction "VCC_1") (pintype "power_in"))
    )
    (net (code "79") (name "VCC_3V3") (class "Default")
      (node (ref "C52") (pin "2") (pinfunction "2_2") (pintype "passive"))
      (node (ref "C75") (pin "2") (pinfunction "2_2") (pintype "passive"))
      (node (ref "P3") (pin "1") (pinfunction "1_1") (pintype "passive"))
      (node (ref "R28") (pin "2") (pinfunction "2_2") (pintype "passive"))
      (node (ref "R30") (pin "2") (pinfunction "2_2") (pintype "passive"))
      (node (ref "SD1") (pin "4") (pinfunction "VDD_4") (pintype "passive"))
      (node (ref "U6") (pin "5") (pinfunction "VIO_5") (pintype "passive"))
      (node (ref "U8") (pin "16") (pinfunction "VCC_16") (pintype "passive"))
      (node (ref "U8") (pin "4") (pinfunction "V3_4") (pintype "passive"))
    )
    (net (code "80") (name "VCC_5V_M") (class "Default")
      (node (ref "P15") (pin "1") (pinfunction "1_1") (pintype "passive"))
      (node (ref "P15") (pin "2") (pinfunction "2_2") (pintype "passive"))
      (node (ref "P15") (pin "3") (pinfunction "3_3") (pintype "passive"))
      (node (ref "P15") (pin "4") (pinfunction "4_4") (pintype "passive"))
      (node (ref "P20") (pin "1") (pinfunction "1_1") (pintype "passive"))
      (node (ref "P20") (pin "2") (pinfunction "2_2") (pintype "passive"))
      (node (ref "P20") (pin "3") (pinfunction "3_3") (pintype "passive"))
      (node (ref "P20") (pin "4") (pinfunction "4_4") (pintype "passive"))
      (node (ref "P25") (pin "1") (pinfunction "1_1") (pintype "passive"))
      (node (ref "P25") (pin "2") (pinfunction "2_2") (pintype "passive"))
      (node (ref "R27") (pin "2") (pinfunction "2_2") (pintype "passive"))
    )
    (net (code "81") (name "VCC_5V_S") (class "Default")
      (node (ref "C53") (pin "1") (pinfunction "1_1") (pintype "passive"))
      (node (ref "LS1") (pin "1") (pinfunction "1_1") (pintype "passive"))
      (node (ref "P28") (pin "1") (pinfunction "1_1") (pintype "passive"))
      (node (ref "P30") (pin "1") (pinfunction "1_1") (pintype "passive"))
      (node (ref "P6") (pin "1") (pinfunction "1_1") (pintype "passive"))
      (node (ref "R26") (pin "2") (pinfunction "2_2") (pintype "passive"))
      (node (ref "U6") (pin "3") (pinfunction "VCC_3") (pintype "passive"))
    )
    (net (code "82") (name "VCC_PW") (class "Default")
      (node (ref "R1") (pin "2") (pinfunction "2_2") (pintype "passive"))
    )
    (net (code "83") (name "unconnected-(MicroUSB-DIP1-ID-Pad4)") (class "Default")
      (node (ref "MicroUSB-DIP1") (pin "4") (pinfunction "ID_4") (pintype "passive"))
    )
    (net (code "84") (name "unconnected-(U8-CTS#-Pad9)") (class "Default")
      (node (ref "U8") (pin "9") (pinfunction "CTS#_9") (pintype "passive"))
    )
    (net (code "85") (name "unconnected-(U8-DCD#-Pad12)") (class "Default")
      (node (ref "U8") (pin "12") (pinfunction "DCD#_12") (pintype "passive"))
    )
    (net (code "86") (name "unconnected-(U8-DSR#-Pad10)") (class "Default")
      (node (ref "U8") (pin "10") (pinfunction "DSR#_10") (pintype "passive"))
    )
    (net (code "87") (name "unconnected-(U8-R232-Pad15)") (class "Default")
      (node (ref "U8") (pin "15") (pinfunction "R232_15") (pintype "passive"))
    )
    (net (code "88") (name "unconnected-(U8-RI#-Pad11)") (class "Default")
      (node (ref "U8") (pin "11") (pinfunction "RI#_11") (pintype "passive"))
    )
    (net (code "89") (name "unconnected-(U8-RTS#-Pad14)") (class "Default")
      (node (ref "U8") (pin "14") (pinfunction "RTS#_14") (pintype "passive"))
    )
    (net (code "90") (name "unconnected-(U8-TDR#-Pad13)") (class "Default")
      (node (ref "U8") (pin "13") (pinfunction "TDR#_13") (pintype "passive"))
    )
  )
)
